# board_1.net
KiCad netlist of a schematic drawn in EAGLE
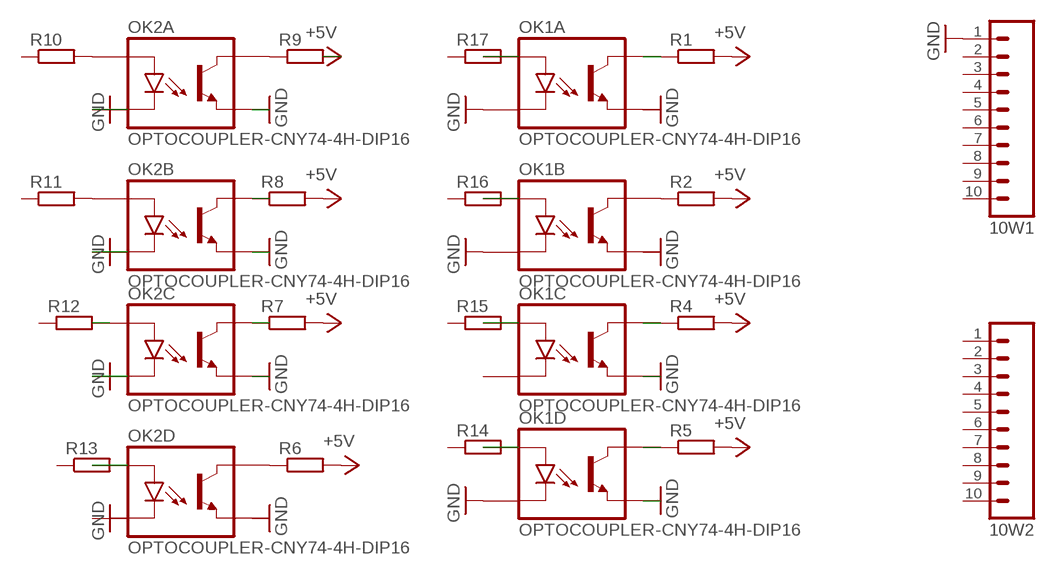
[diagram p0: schematic, sheet 1]

(export (version "E")
  (design (tool "Eeschema 10.0.6"))
  (components
    (comp (ref "10W1")
      (value "M10")
      (footprint "eagle-import:10P")
      (libsource (lib "eagle-import") (part "M10"))
    )
    (comp (ref "10W2")
      (value "M10")
      (footprint "eagle-import:10P")
      (libsource (lib "eagle-import") (part "M10"))
    )
    (comp (ref "OK1")
      (value "OPTOCOUPLER-CNY74-4H-DIP16")
      (footprint "eagle-import:DIL16-3")
      (libsource (lib "eagle-import") (part "OPTOCOUPLER-CNY74-4H-DIP16"))
    )
    (comp (ref "OK2")
      (value "OPTOCOUPLER-CNY74-4H-DIP16")
      (footprint "eagle-import:DIL16-3")
      (libsource (lib "eagle-import") (part "OPTOCOUPLER-CNY74-4H-DIP16"))
    )
    (comp (ref "R1")
      (value "R-EU_0207/7")
      (footprint "eagle-import:0207_7")
      (libsource (lib "eagle-import") (part "R-EU_0207/7"))
    )
    (comp (ref "R2")
      (value "R-EU_0207/7")
      (footprint "eagle-import:0207_7")
      (libsource (lib "eagle-import") (part "R-EU_0207/7"))
    )
    (comp (ref "R4")
      (value "R-EU_0207/7")
      (footprint "eagle-import:0207_7")
      (libsource (lib "eagle-import") (part "R-EU_0207/7"))
    )
    (comp (ref "R5")
      (value "R-EU_0207/7")
      (footprint "eagle-import:0207_7")
      (libsource (lib "eagle-import") (part "R-EU_0207/7"))
    )
    (comp (ref "R6")
      (value "R-EU_0207/7")
      (footprint "eagle-import:0207_7")
      (libsource (lib "eagle-import") (part "R-EU_0207/7"))
    )
    (comp (ref "R7")
      (value "R-EU_0207/7")
      (footprint "eagle-import:0207_7")
      (libsource (lib "eagle-import") (part "R-EU_0207/7"))
    )
    (comp (ref "R8")
      (value "R-EU_0207/7")
      (footprint "eagle-import:0207_7")
      (libsource (lib "eagle-import") (part "R-EU_0207/7"))
    )
    (comp (ref "R9")
      (value "R-EU_0207/7")
      (footprint "eagle-import:0207_7")
      (libsource (lib "eagle-import") (part "R-EU_0207/7"))
    )
    (comp (ref "R10")
      (value "R-EU_0207/7")
      (footprint "eagle-import:0207_7")
      (libsource (lib "eagle-import") (part "R-EU_0207/7"))
    )
    (comp (ref "R11")
      (value "R-EU_0207/7")
      (footprint "eagle-import:0207_7")
      (libsource (lib "eagle-import") (part "R-EU_0207/7"))
    )
    (comp (ref "R12")
      (value "R-EU_0207/7")
      (footprint "eagle-import:0207_7")
      (libsource (lib "eagle-import") (part "R-EU_0207/7"))
    )
    (comp (ref "R13")
      (value "R-EU_0207/7")
      (footprint "eagle-import:0207_7")
      (libsource (lib "eagle-import") (part "R-EU_0207/7"))
    )
    (comp (ref "R14")
      (value "R-EU_0207/7")
      (footprint "eagle-import:0207_7")
      (libsource (lib "eagle-import") (part "R-EU_0207/7"))
    )
    (comp (ref "R15")
      (value "R-EU_0207/7")
      (footprint "eagle-import:0207_7")
      (libsource (lib "eagle-import") (part "R-EU_0207/7"))
    )
    (comp (ref "R16")
      (value "R-EU_0207/7")
      (footprint "eagle-import:0207_7")
      (libsource (lib "eagle-import") (part "R-EU_0207/7"))
    )
    (comp (ref "R17")
      (value "R-EU_0207/7")
      (footprint "eagle-import:0207_7")
      (libsource (lib "eagle-import") (part "R-EU_0207/7"))
    )
  )
  (nets
    (net (code "1") (name "+5V") (class "Default")
      (node (ref "R1") (pin "2") (pinfunction "2_2") (pintype "passive"))
      (node (ref "R2") (pin "2") (pinfunction "2_2") (pintype "passive"))
      (node (ref "R4") (pin "2") (pinfunction "2_2") (pintype "passive"))
      (node (ref "R5") (pin "2") (pinfunction "2_2") (pintype "passive"))
      (node (ref "R6") (pin "2") (pinfunction "2_2") (pintype "passive"))
      (node (ref "R7") (pin "2") (pinfunction "2_2") (pintype "passive"))
      (node (ref "R8") (pin "2") (pinfunction "2_2") (pintype "passive"))
      (node (ref "R9") (pin "2") (pinfunction "2_2") (pintype "passive"))
    )
    (net (code "2") (name "GND") (class "Default")
      (node (ref "10W1") (pin "1") (pinfunction "1_1") (pintype "passive"))
      (node (ref "OK1") (pin "10") (pinfunction "EMITTER1_10") (pintype "passive"))
      (node (ref "OK1") (pin "12") (pinfunction "EMITTER1_12") (pintype "passive"))
      (node (ref "OK1") (pin "2") (pinfunction "C1_2") (pintype "passive"))
      (node (ref "OK1") (pin "3") (pinfunction "C1_3") (pintype "passive"))
      (node (ref "OK1") (pin "7") (pinfunction "C1_7") (pintype "passive"))
      (node (ref "OK2") (pin "12") (pinfunction "EMITTER1_12") (pintype "passive"))
      (node (ref "OK2") (pin "13") (pinfunction "EMITTER1_13") (pintype "passive"))
      (node (ref "OK2") (pin "16") (pinfunction "EMITTER1_16") (pintype "passive"))
      (node (ref "OK2") (pin "2") (pinfunction "C1_2") (pintype "passive"))
      (node (ref "OK2") (pin "3") (pinfunction "C1_3") (pintype "passive"))
      (node (ref "OK2") (pin "6") (pinfunction "C1_6") (pintype "passive"))
    )
    (net (code "3") (name "Net-(OK1A-A1)") (class "Default")
      (node (ref "OK1") (pin "1") (pinfunction "A1_1") (pintype "passive"))
      (node (ref "R17") (pin "2") (pinfunction "2_2") (pintype "passive"))
    )
    (net (code "4") (name "Net-(OK1A-COLLECTOR1)") (class "Default")
      (node (ref "OK1") (pin "15") (pinfunction "COLLECTOR1_15") (pintype "passive"))
      (node (ref "R1") (pin "1") (pinfunction "1_1") (pintype "passive"))
    )
    (net (code "5") (name "Net-(OK1B-A1)") (class "Default")
      (node (ref "OK1") (pin "4") (pinfunction "A1_4") (pintype "passive"))
      (node (ref "R16") (pin "2") (pinfunction "2_2") (pintype "passive"))
    )
    (net (code "6") (name "Net-(OK1B-COLLECTOR1)") (class "Default")
      (node (ref "OK1") (pin "14") (pinfunction "COLLECTOR1_14") (pintype "passive"))
      (node (ref "R2") (pin "1") (pinfunction "1_1") (pintype "passive"))
    )
    (net (code "7") (name "Net-(OK1C-A1)") (class "Default")
      (node (ref "OK1") (pin "5") (pinfunction "A1_5") (pintype "passive"))
      (node (ref "R15") (pin "2") (pinfunction "2_2") (pintype "passive"))
    )
    (net (code "8") (name "Net-(OK1C-COLLECTOR1)") (class "Default")
      (node (ref "OK1") (pin "11") (pinfunction "COLLECTOR1_11") (pintype "passive"))
      (node (ref "R4") (pin "1") (pinfunction "1_1") (pintype "passive"))
    )
    (net (code "9") (name "Net-(OK1D-A1)") (class "Default")
      (node (ref "OK1") (pin "8") (pinfunction "A1_8") (pintype "passive"))
      (node (ref "R14") (pin "2") (pinfunction "2_2") (pintype "passive"))
    )
    (net (code "10") (name "Net-(OK1D-COLLECTOR1)") (class "Default")
      (node (ref "OK1") (pin "9") (pinfunction "COLLECTOR1_9") (pintype "passive"))
      (node (ref "R5") (pin "1") (pinfunction "1_1") (pintype "passive"))
    )
    (net (code "11") (name "Net-(OK2A-A1)") (class "Default")
      (node (ref "OK2") (pin "1") (pinfunction "A1_1") (pintype "passive"))
      (node (ref "R10") (pin "2") (pinfunction "2_2") (pintype "passive"))
    )
    (net (code "12") (name "Net-(OK2A-COLLECTOR1)") (class "Default")
      (node (ref "OK2") (pin "15") (pinfunction "COLLECTOR1_15") (pintype "passive"))
      (node (ref "R9") (pin "1") (pinfunction "1_1") (pintype "passive"))
    )
    (net (code "13") (name "Net-(OK2B-A1)") (class "Default")
      (node (ref "OK2") (pin "4") (pinfunction "A1_4") (pintype "passive"))
      (node (ref "R11") (pin "2") (pinfunction "2_2") (pintype "passive"))
    )
    (net (code "14") (name "Net-(OK2B-COLLECTOR1)") (class "Default")
      (node (ref "OK2") (pin "14") (pinfunction "COLLECTOR1_14") (pintype "passive"))
      (node (ref "R8") (pin "1") (pinfunction "1_1") (pintype "passive"))
    )
    (net (code "15") (name "Net-(OK2C-A1)") (class "Default")
      (node (ref "OK2") (pin "5") (pinfunction "A1_5") (pintype "passive"))
      (node (ref "R12") (pin "2") (pinfunction "2_2") (pintype "passive"))
    )
    (net (code "16") (name "Net-(OK2C-COLLECTOR1)") (class "Default")
      (node (ref "OK2") (pin "11") (pinfunction "COLLECTOR1_11") (pintype "passive"))
      (node (ref "R7") (pin "1") (pinfunction "1_1") (pintype "passive"))
    )
    (net (code "17") (name "Net-(OK2D-A1)") (class "Default")
      (node (ref "OK2") (pin "8") (pinfunction "A1_8") (pintype "passive"))
      (node (ref "R13") (pin "2") (pinfunction "2_2") (pintype "passive"))
    )
    (net (code "18") (name "Net-(OK2D-COLLECTOR1)") (class "Default")
      (node (ref "OK2") (pin "9") (pinfunction "COLLECTOR1_9") (pintype "passive"))
      (node (ref "R6") (pin "1") (pinfunction "1_1") (pintype "passive"))
    )
    (net (code "19") (name "unconnected-(10W1-Pad2)") (class "Default")
      (node (ref "10W1") (pin "2") (pinfunction "2_2") (pintype "passive"))
    )
    (net (code "20") (name "unconnected-(10W1-Pad3)") (class "Default")
      (node (ref "10W1") (pin "3") (pinfunction "3_3") (pintype "passive"))
    )
    (net (code "21") (name "unconnected-(10W1-Pad4)") (class "Default")
      (node (ref "10W1") (pin "4") (pinfunction "4_4") (pintype "passive"))
    )
    (net (code "22") (name "unconnected-(10W1-Pad5)") (class "Default")
      (node (ref "10W1") (pin "5") (pinfunction "5_5") (pintype "passive"))
    )
    (net (code "23") (name "unconnected-(10W1-Pad6)") (class "Default")
      (node (ref "10W1") (pin "6") (pinfunction "6_6") (pintype "passive"))
    )
    (net (code "24") (name "unconnected-(10W1-Pad7)") (class "Default")
      (node (ref "10W1") (pin "7") (pinfunction "7_7") (pintype "passive"))
    )
    (net (code "25") (name "unconnected-(10W1-Pad8)") (class "Default")
      (node (ref "10W1") (pin "8") (pinfunction "8_8") (pintype "passive"))
    )
    (net (code "26") (name "unconnected-(10W1-Pad9)") (class "Default")
      (node (ref "10W1") (pin "9") (pinfunction "9_9") (pintype "passive"))
    )
    (net (code "27") (name "unconnected-(10W1-Pad10)") (class "Default")
      (node (ref "10W1") (pin "10") (pinfunction "10_10") (pintype "passive"))
    )
    (net (code "28") (name "unconnected-(10W2-Pad1)") (class "Default")
      (node (ref "10W2") (pin "1") (pinfunction "1_1") (pintype "passive"))
    )
    (net (code "29") (name "unconnected-(10W2-Pad2)") (class "Default")
      (node (ref "10W2") (pin "2") (pinfunction "2_2") (pintype "passive"))
    )
    (net (code "30") (name "unconnected-(10W2-Pad3)") (class "Default")
      (node (ref "10W2") (pin "3") (pinfunction "3_3") (pintype "passive"))
    )
    (net (code "31") (name "unconnected-(10W2-Pad4)") (class "Default")
      (node (ref "10W2") (pin "4") (pinfunction "4_4") (pintype "passive"))
    )
    (net (code "32") (name "unconnected-(10W2-Pad5)") (class "Default")
      (node (ref "10W2") (pin "5") (pinfunction "5_5") (pintype "passive"))
    )
    (net (code "33") (name "unconnected-(10W2-Pad6)") (class "Default")
      (node (ref "10W2") (pin "6") (pinfunction "6_6") (pintype "passive"))
    )
    (net (code "34") (name "unconnected-(10W2-Pad7)") (class "Default")
      (node (ref "10W2") (pin "7") (pinfunction "7_7") (pintype "passive"))
    )
    (net (code "35") (name "unconnected-(10W2-Pad8)") (class "Default")
      (node (ref "10W2") (pin "8") (pinfunction "8_8") (pintype "passive"))
    )
    (net (code "36") (name "unconnected-(10W2-Pad9)") (class "Default")
      (node (ref "10W2") (pin "9") (pinfunction "9_9") (pintype "passive"))
    )
    (net (code "37") (name "unconnected-(10W2-Pad10)") (class "Default")
      (node (ref "10W2") (pin "10") (pinfunction "10_10") (pintype "passive"))
    )
    (net (code "38") (name "unconnected-(OK1A-EMITTER1-Pad16)") (class "Default")
      (node (ref "OK1") (pin "16") (pinfunction "EMITTER1_16") (pintype "passive"))
    )
    (net (code "39") (name "unconnected-(OK1B-EMITTER1-Pad13)") (class "Default")
      (node (ref "OK1") (pin "13") (pinfunction "EMITTER1_13") (pintype "passive"))
    )
    (net (code "40") (name "unconnected-(OK1C-C1-Pad6)") (class "Default")
      (node (ref "OK1") (pin "6") (pinfunction "C1_6") (pintype "passive"))
    )
    (net (code "41") (name "unconnected-(OK2D-C1-Pad7)") (class "Default")
      (node (ref "OK2") (pin "7") (pinfunction "C1_7") (pintype "passive"))
    )
    (net (code "42") (name "unconnected-(OK2D-EMITTER1-Pad10)") (class "Default")
      (node (ref "OK2") (pin "10") (pinfunction "EMITTER1_10") (pintype "passive"))
    )
    (net (code "43") (name "unconnected-(R10-Pad1)") (class "Default")
      (node (ref "R10") (pin "1") (pinfunction "1_1") (pintype "passive"))
    )
    (net (code "44") (name "unconnected-(R11-Pad1)") (class "Default")
      (node (ref "R11") (pin "1") (pinfunction "1_1") (pintype "passive"))
    )
    (net (code "45") (name "unconnected-(R12-Pad1)") (class "Default")
      (node (ref "R12") (pin "1") (pinfunction "1_1") (pintype "passive"))
    )
    (net (code "46") (name "unconnected-(R13-Pad1)") (class "Default")
      (node (ref "R13") (pin "1") (pinfunction "1_1") (pintype "passive"))
    )
    (net (code "47") (name "unconnected-(R14-Pad1)") (class "Default")
      (node (ref "R14") (pin "1") (pinfunction "1_1") (pintype "passive"))
    )
    (net (code "48") (name "unconnected-(R15-Pad1)") (class "Default")
      (node (ref "R15") (pin "1") (pinfunction "1_1") (pintype "passive"))
    )
    (net (code "49") (name "unconnected-(R16-Pad1)") (class "Default")
      (node (ref "R16") (pin "1") (pinfunction "1_1") (pintype "passive"))
    )
    (net (code "50") (name "unconnected-(R17-Pad1)") (class "Default")
      (node (ref "R17") (pin "1") (pinfunction "1_1") (pintype "passive"))
    )
  )
)
